# OLX_FOH_Lights.net
KiCad netlist of a schematic drawn in EAGLE
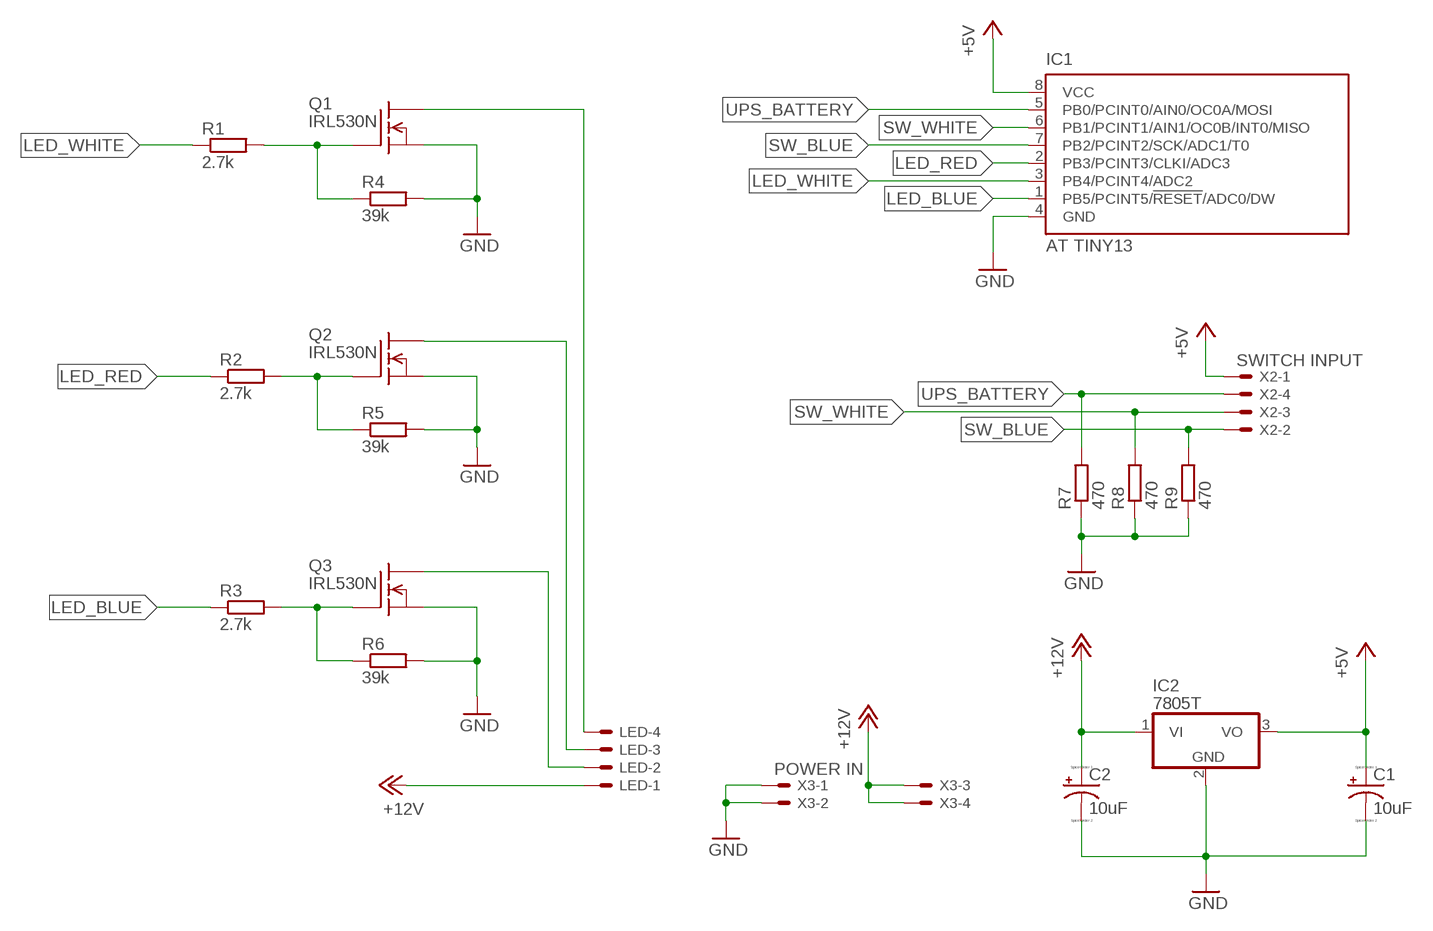
[diagram p0: schematic, sheet 1]

(export (version "E")
  (design (tool "Eeschema 10.0.6"))
  (components
    (comp (ref "C1")
      (value "10uF")
      (footprint "eagle-import:TT2D4")
      (libsource (lib "eagle-import") (part "CPOL-USTT2D4"))
    )
    (comp (ref "C2")
      (value "10uF")
      (footprint "eagle-import:TT2D4")
      (libsource (lib "eagle-import") (part "CPOL-USTT2D4"))
    )
    (comp (ref "IC1")
      (value "AT TINY13")
      (footprint "eagle-import:DIL08")
      (fields (field (name "MPN") "ATTINY13-20PU"))
      (libsource (lib "eagle-import") (part "TINY13PU-20"))
    )
    (comp (ref "IC2")
      (value "7805T")
      (footprint "eagle-import:TO220H")
      (libsource (lib "eagle-import") (part "78T05"))
    )
    (comp (ref "LED")
      (value "LED OUTPUT")
      (footprint "eagle-import:22-23-2041")
      (fields (field (name "MF") "MOLEX") (field (name "MPN") "22-23-2041"))
      (libsource (lib "eagle-import") (part "22-23-2041"))
    )
    (comp (ref "Q1")
      (value "IRL530N")
      (footprint "eagle-import:TO220")
      (libsource (lib "eagle-import") (part "BUZ10"))
    )
    (comp (ref "Q2")
      (value "IRL530N")
      (footprint "eagle-import:TO220")
      (libsource (lib "eagle-import") (part "BUZ10"))
    )
    (comp (ref "Q3")
      (value "IRL530N")
      (footprint "eagle-import:TO220")
      (libsource (lib "eagle-import") (part "BUZ10"))
    )
    (comp (ref "R1")
      (value "2.7k")
      (footprint "eagle-import:0411_12")
      (libsource (lib "eagle-import") (part "R-EU_0411/12"))
    )
    (comp (ref "R2")
      (value "2.7k")
      (footprint "eagle-import:0411_12")
      (libsource (lib "eagle-import") (part "R-EU_0411/12"))
    )
    (comp (ref "R3")
      (value "2.7k")
      (footprint "eagle-import:0411_12")
      (libsource (lib "eagle-import") (part "R-EU_0411/12"))
    )
    (comp (ref "R4")
      (value "39k")
      (footprint "eagle-import:0411_12")
      (libsource (lib "eagle-import") (part "R-EU_0411/12"))
    )
    (comp (ref "R5")
      (value "39k")
      (footprint "eagle-import:0411_12")
      (libsource (lib "eagle-import") (part "R-EU_0411/12"))
    )
    (comp (ref "R6")
      (value "39k")
      (footprint "eagle-import:0411_12")
      (libsource (lib "eagle-import") (part "R-EU_0411/12"))
    )
    (comp (ref "R7")
      (value "470")
      (footprint "eagle-import:0411_12")
      (libsource (lib "eagle-import") (part "R-EU_0411/12"))
    )
    (comp (ref "R8")
      (value "470")
      (footprint "eagle-import:0411_12")
      (libsource (lib "eagle-import") (part "R-EU_0411/12"))
    )
    (comp (ref "R9")
      (value "470")
      (footprint "eagle-import:0411_12")
      (libsource (lib "eagle-import") (part "R-EU_0411/12"))
    )
    (comp (ref "X2")
      (value "SWITCH INPUT")
      (footprint "eagle-import:22-23-2041")
      (fields (field (name "MF") "MOLEX") (field (name "MPN") "22-23-2041"))
      (libsource (lib "eagle-import") (part "22-23-2041"))
    )
    (comp (ref "X3")
      (value "POWER IN")
      (footprint "eagle-import:22-23-2041")
      (fields (field (name "MF") "MOLEX") (field (name "MPN") "22-23-2041"))
      (libsource (lib "eagle-import") (part "22-23-2041"))
    )
  )
  (nets
    (net (code "1") (name "+5V") (class "Default")
      (node (ref "C1") (pin "+") (pinfunction "+_+") (pintype "passive"))
      (node (ref "IC1") (pin "8") (pinfunction "VCC_8") (pintype "power_in"))
      (node (ref "IC2") (pin "3") (pinfunction "VO_3") (pintype "passive"))
      (node (ref "X2") (pin "1") (pinfunction "S_1") (pintype "passive"))
    )
    (net (code "2") (name "+12V") (class "Default")
      (node (ref "C2") (pin "+") (pinfunction "+_+") (pintype "passive"))
      (node (ref "IC2") (pin "1") (pinfunction "VI_1") (pintype "input"))
      (node (ref "LED") (pin "1") (pinfunction "S_1") (pintype "passive"))
      (node (ref "X3") (pin "3") (pinfunction "S_3") (pintype "passive"))
      (node (ref "X3") (pin "4") (pinfunction "S_4") (pintype "passive"))
    )
    (net (code "3") (name "GND") (class "Default")
      (node (ref "C1") (pin "-") (pinfunction "-_-") (pintype "passive"))
      (node (ref "C2") (pin "-") (pinfunction "-_-") (pintype "passive"))
      (node (ref "IC1") (pin "4") (pinfunction "GND_4") (pintype "power_in"))
      (node (ref "IC2") (pin "2") (pinfunction "GND_2") (pintype "passive"))
      (node (ref "Q1") (pin "3") (pinfunction "S_3") (pintype "passive"))
      (node (ref "Q2") (pin "3") (pinfunction "S_3") (pintype "passive"))
      (node (ref "Q3") (pin "3") (pinfunction "S_3") (pintype "passive"))
      (node (ref "R4") (pin "2") (pinfunction "2_2") (pintype "passive"))
      (node (ref "R5") (pin "2") (pinfunction "2_2") (pintype "passive"))
      (node (ref "R6") (pin "2") (pinfunction "2_2") (pintype "passive"))
      (node (ref "R7") (pin "1") (pinfunction "1_1") (pintype "passive"))
      (node (ref "R8") (pin "1") (pinfunction "1_1") (pintype "passive"))
      (node (ref "R9") (pin "1") (pinfunction "1_1") (pintype "passive"))
      (node (ref "X3") (pin "1") (pinfunction "S_1") (pintype "passive"))
      (node (ref "X3") (pin "2") (pinfunction "S_2") (pintype "passive"))
    )
    (net (code "4") (name "LED_BLUE") (class "Default")
      (node (ref "IC1") (pin "1") (pinfunction "PB5/PCINT5/~{RESET}/ADC0/DW_1") (pintype "bidirectional"))
      (node (ref "R3") (pin "1") (pinfunction "1_1") (pintype "passive"))
    )
    (net (code "5") (name "LED_RED") (class "Default")
      (node (ref "IC1") (pin "2") (pinfunction "PB3/PCINT3/CLKI/ADC3_2") (pintype "bidirectional"))
      (node (ref "R2") (pin "1") (pinfunction "1_1") (pintype "passive"))
    )
    (net (code "6") (name "LED_WHITE") (class "Default")
      (node (ref "IC1") (pin "3") (pinfunction "PB4/PCINT4/ADC2_3") (pintype "bidirectional"))
      (node (ref "R1") (pin "1") (pinfunction "1_1") (pintype "passive"))
    )
    (net (code "7") (name "Net-(LEDB-S)") (class "Default")
      (node (ref "LED") (pin "2") (pinfunction "S_2") (pintype "passive"))
      (node (ref "Q3") (pin "2") (pinfunction "D_2") (pintype "passive"))
    )
    (net (code "8") (name "Net-(LEDC-S)") (class "Default")
      (node (ref "LED") (pin "3") (pinfunction "S_3") (pintype "passive"))
      (node (ref "Q2") (pin "2") (pinfunction "D_2") (pintype "passive"))
    )
    (net (code "9") (name "Net-(LEDD-S)") (class "Default")
      (node (ref "LED") (pin "4") (pinfunction "S_4") (pintype "passive"))
      (node (ref "Q1") (pin "2") (pinfunction "D_2") (pintype "passive"))
    )
    (net (code "10") (name "Net-(Q1-G)") (class "Default")
      (node (ref "Q1") (pin "1") (pinfunction "G_1") (pintype "passive"))
      (node (ref "R1") (pin "2") (pinfunction "2_2") (pintype "passive"))
      (node (ref "R4") (pin "1") (pinfunction "1_1") (pintype "passive"))
    )
    (net (code "11") (name "Net-(Q2-G)") (class "Default")
      (node (ref "Q2") (pin "1") (pinfunction "G_1") (pintype "passive"))
      (node (ref "R2") (pin "2") (pinfunction "2_2") (pintype "passive"))
      (node (ref "R5") (pin "1") (pinfunction "1_1") (pintype "passive"))
    )
    (net (code "12") (name "Net-(Q3-G)") (class "Default")
      (node (ref "Q3") (pin "1") (pinfunction "G_1") (pintype "passive"))
      (node (ref "R3") (pin "2") (pinfunction "2_2") (pintype "passive"))
      (node (ref "R6") (pin "1") (pinfunction "1_1") (pintype "passive"))
    )
    (net (code "13") (name "SW_BLUE") (class "Default")
      (node (ref "IC1") (pin "7") (pinfunction "PB2/PCINT2/SCK/ADC1/T0_7") (pintype "bidirectional"))
      (node (ref "R9") (pin "2") (pinfunction "2_2") (pintype "passive"))
      (node (ref "X2") (pin "2") (pinfunction "S_2") (pintype "passive"))
    )
    (net (code "14") (name "SW_WHITE") (class "Default")
      (node (ref "IC1") (pin "6") (pinfunction "PB1/PCINT1/AIN1/OC0B/INT0/MISO_6") (pintype "bidirectional"))
      (node (ref "R8") (pin "2") (pinfunction "2_2") (pintype "passive"))
      (node (ref "X2") (pin "3") (pinfunction "S_3") (pintype "passive"))
    )
    (net (code "15") (name "UPS_BATTERY") (class "Default")
      (node (ref "IC1") (pin "5") (pinfunction "PB0/PCINT0/AIN0/OC0A/MOSI_5") (pintype "bidirectional"))
      (node (ref "R7") (pin "2") (pinfunction "2_2") (pintype "passive"))
      (node (ref "X2") (pin "4") (pinfunction "S_4") (pintype "passive"))
    )
  )
)
